# LED-Cube_v2.net
KiCad netlist of a schematic drawn in EAGLE
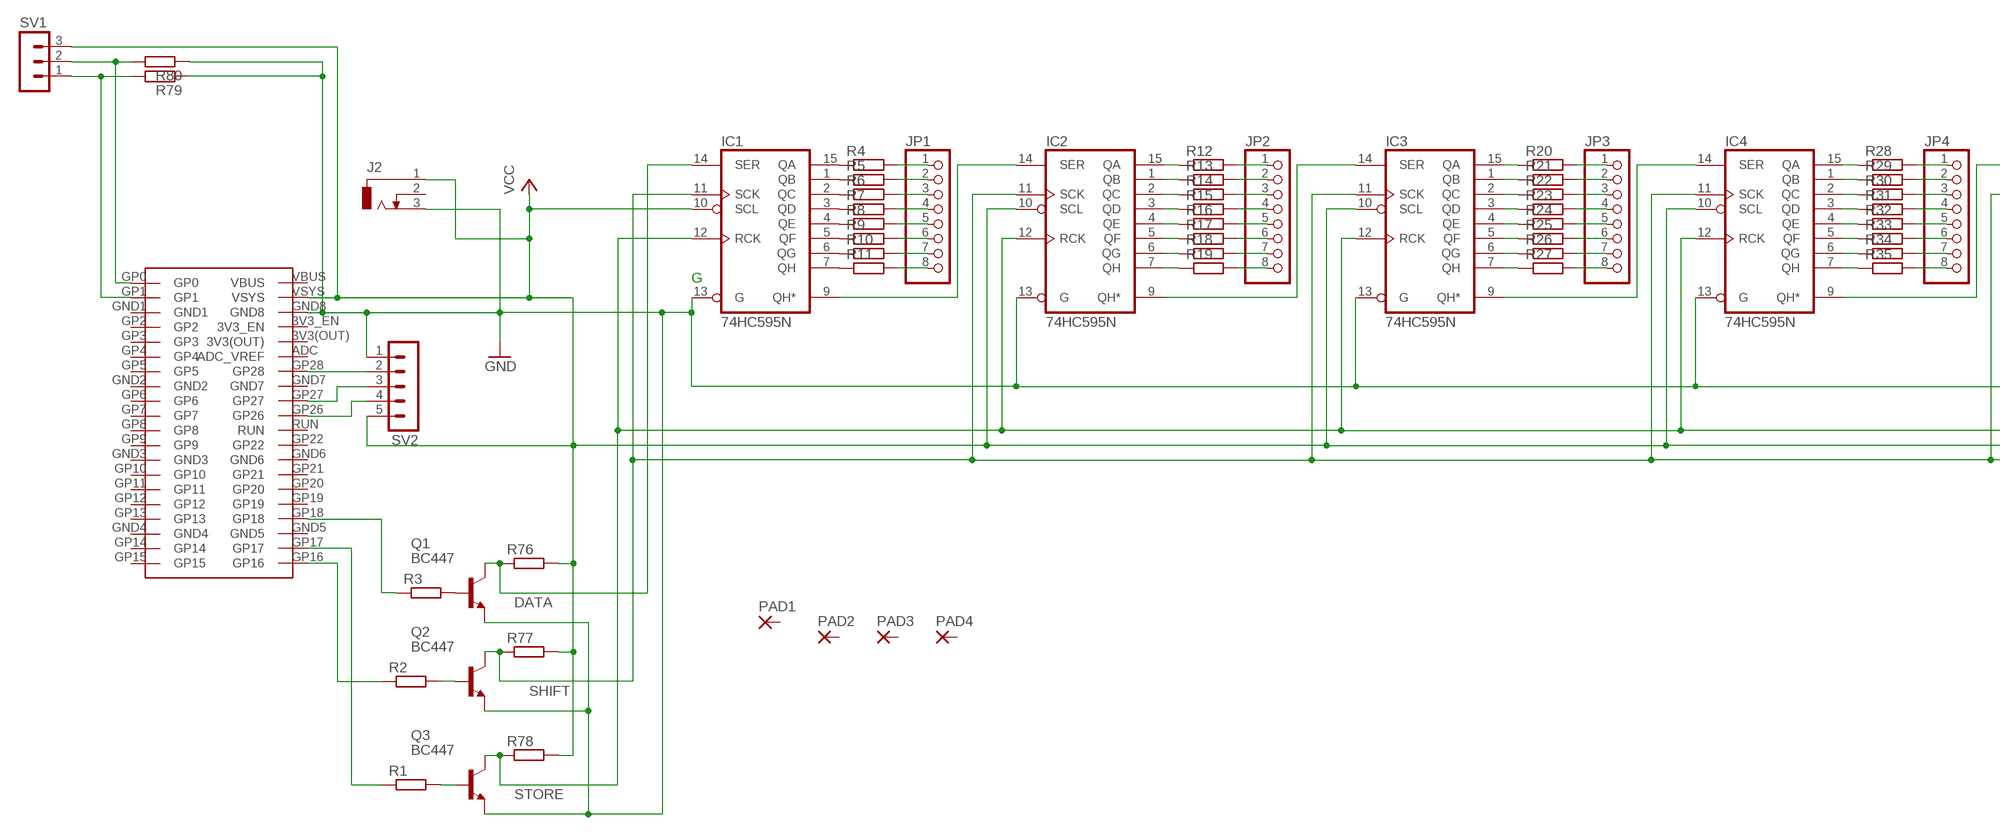
[diagram p0: schematic, sheet 1, part 1 of 2]
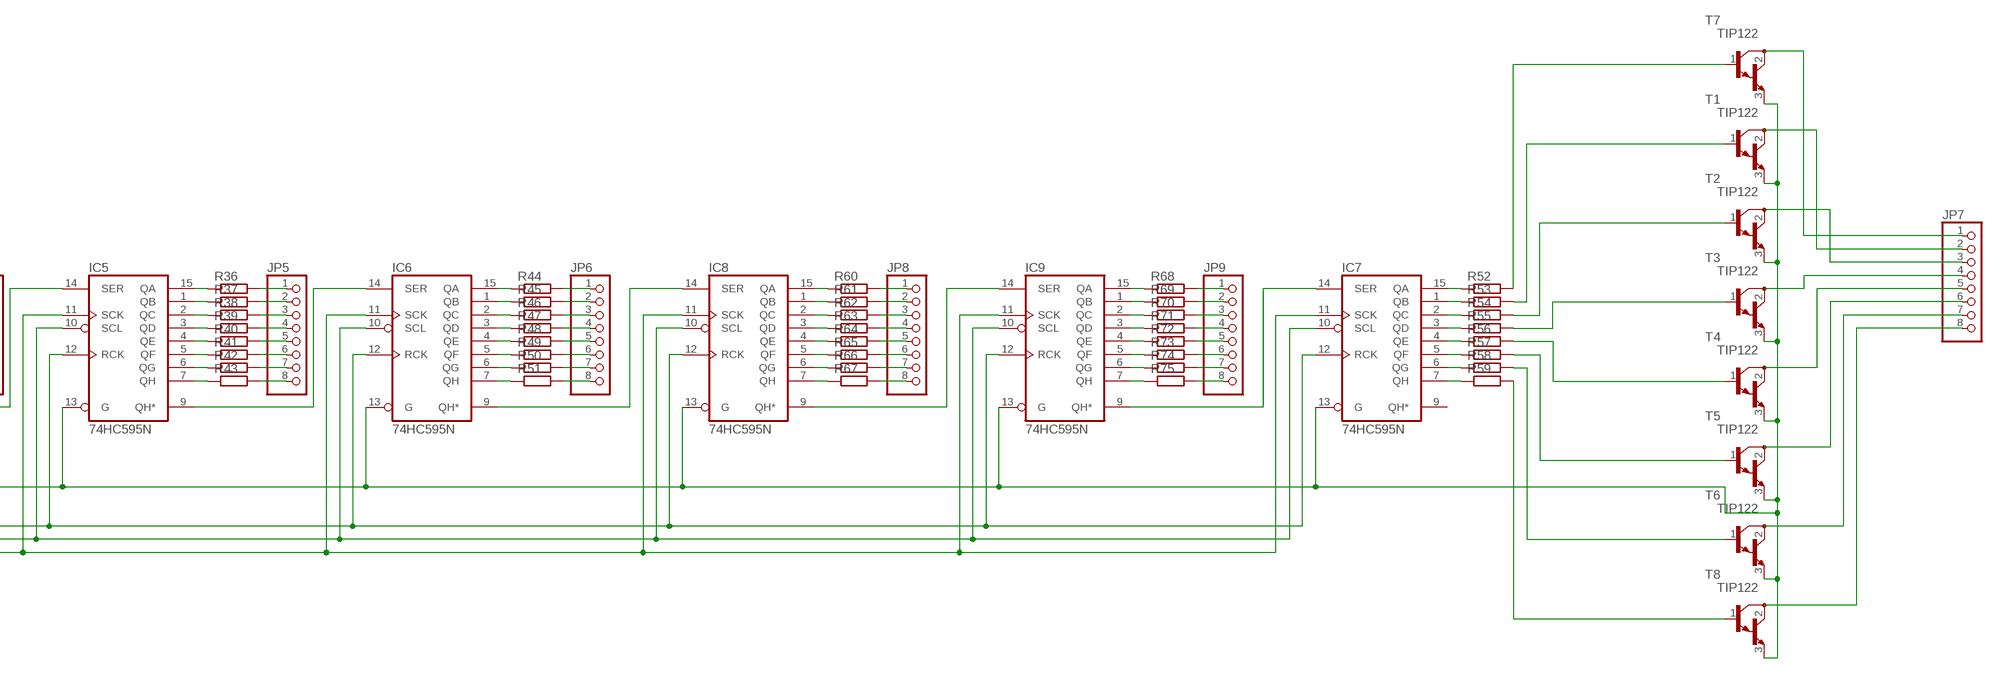
[diagram p1: schematic, sheet 1, part 2 of 2]

(export (version "E")
  (design (tool "Eeschema 10.0.6"))
  (components
    (comp (ref "IC1")
      (value "74HC595N")
      (footprint "eagle-import:DIL16")
      (libsource (lib "eagle-import") (part "74595NHC"))
    )
    (comp (ref "IC2")
      (value "74HC595N")
      (footprint "eagle-import:DIL16")
      (libsource (lib "eagle-import") (part "74595NHC"))
    )
    (comp (ref "IC3")
      (value "74HC595N")
      (footprint "eagle-import:DIL16")
      (libsource (lib "eagle-import") (part "74595NHC"))
    )
    (comp (ref "IC4")
      (value "74HC595N")
      (footprint "eagle-import:DIL16")
      (libsource (lib "eagle-import") (part "74595NHC"))
    )
    (comp (ref "IC5")
      (value "74HC595N")
      (footprint "eagle-import:DIL16")
      (libsource (lib "eagle-import") (part "74595NHC"))
    )
    (comp (ref "IC6")
      (value "74HC595N")
      (footprint "eagle-import:DIL16")
      (libsource (lib "eagle-import") (part "74595NHC"))
    )
    (comp (ref "IC7")
      (value "74HC595N")
      (footprint "eagle-import:DIL16")
      (libsource (lib "eagle-import") (part "74595NHC"))
    )
    (comp (ref "IC8")
      (value "74HC595N")
      (footprint "eagle-import:DIL16")
      (libsource (lib "eagle-import") (part "74595NHC"))
    )
    (comp (ref "IC9")
      (value "74HC595N")
      (footprint "eagle-import:DIL16")
      (libsource (lib "eagle-import") (part "74595NHC"))
    )
    (comp (ref "J2")
      (value "DCJ0303")
      (footprint "eagle-import:DCJ0303")
      (libsource (lib "eagle-import") (part "DCJ0303"))
    )
    (comp (ref "JP1")
      (value "PINHD-1X8")
      (footprint "eagle-import:1X08")
      (libsource (lib "eagle-import") (part "PINHD-1X8"))
    )
    (comp (ref "JP2")
      (value "PINHD-1X8")
      (footprint "eagle-import:1X08")
      (libsource (lib "eagle-import") (part "PINHD-1X8"))
    )
    (comp (ref "JP3")
      (value "PINHD-1X8")
      (footprint "eagle-import:1X08")
      (libsource (lib "eagle-import") (part "PINHD-1X8"))
    )
    (comp (ref "JP4")
      (value "PINHD-1X8")
      (footprint "eagle-import:1X08")
      (libsource (lib "eagle-import") (part "PINHD-1X8"))
    )
    (comp (ref "JP5")
      (value "PINHD-1X8")
      (footprint "eagle-import:1X08")
      (libsource (lib "eagle-import") (part "PINHD-1X8"))
    )
    (comp (ref "JP6")
      (value "PINHD-1X8")
      (footprint "eagle-import:1X08")
      (libsource (lib "eagle-import") (part "PINHD-1X8"))
    )
    (comp (ref "JP7")
      (value "PINHD-1X8")
      (footprint "eagle-import:1X08")
      (libsource (lib "eagle-import") (part "PINHD-1X8"))
    )
    (comp (ref "JP8")
      (value "PINHD-1X8")
      (footprint "eagle-import:1X08")
      (libsource (lib "eagle-import") (part "PINHD-1X8"))
    )
    (comp (ref "JP9")
      (value "PINHD-1X8")
      (footprint "eagle-import:1X08")
      (libsource (lib "eagle-import") (part "PINHD-1X8"))
    )
    (comp (ref "PAD1")
      (value "3,81/1,4")
      (footprint "eagle-import:3,81_1,4")
      (libsource (lib "eagle-import") (part "3,81/1,4"))
    )
    (comp (ref "PAD2")
      (value "3,81/1,4")
      (footprint "eagle-import:3,81_1,4")
      (libsource (lib "eagle-import") (part "3,81/1,4"))
    )
    (comp (ref "PAD3")
      (value "3,81/1,4")
      (footprint "eagle-import:3,81_1,4")
      (libsource (lib "eagle-import") (part "3,81/1,4"))
    )
    (comp (ref "PAD4")
      (value "3,81/1,4")
      (footprint "eagle-import:3,81_1,4")
      (libsource (lib "eagle-import") (part "3,81/1,4"))
    )
    (comp (ref "Q1")
      (value "BC447")
      (footprint "eagle-import:TO92-EBC")
      (libsource (lib "eagle-import") (part "BC447"))
    )
    (comp (ref "Q2")
      (value "BC447")
      (footprint "eagle-import:TO92-EBC")
      (libsource (lib "eagle-import") (part "BC447"))
    )
    (comp (ref "Q3")
      (value "BC447")
      (footprint "eagle-import:TO92-EBC")
      (libsource (lib "eagle-import") (part "BC447"))
    )
    (comp (ref "R1")
      (value "R-EU_0207/10")
      (footprint "eagle-import:0207_10")
      (libsource (lib "eagle-import") (part "R-EU_0207/10"))
    )
    (comp (ref "R2")
      (value "R-EU_0207/10")
      (footprint "eagle-import:0207_10")
      (libsource (lib "eagle-import") (part "R-EU_0207/10"))
    )
    (comp (ref "R3")
      (value "R-EU_0207/10")
      (footprint "eagle-import:0207_10")
      (libsource (lib "eagle-import") (part "R-EU_0207/10"))
    )
    (comp (ref "R4")
      (value "R-EU_0207/10")
      (footprint "eagle-import:0207_10")
      (libsource (lib "eagle-import") (part "R-EU_0207/10"))
    )
    (comp (ref "R5")
      (value "R-EU_0207/10")
      (footprint "eagle-import:0207_10")
      (libsource (lib "eagle-import") (part "R-EU_0207/10"))
    )
    (comp (ref "R6")
      (value "R-EU_0207/10")
      (footprint "eagle-import:0207_10")
      (libsource (lib "eagle-import") (part "R-EU_0207/10"))
    )
    (comp (ref "R7")
      (value "R-EU_0207/10")
      (footprint "eagle-import:0207_10")
      (libsource (lib "eagle-import") (part "R-EU_0207/10"))
    )
    (comp (ref "R8")
      (value "R-EU_0207/10")
      (footprint "eagle-import:0207_10")
      (libsource (lib "eagle-import") (part "R-EU_0207/10"))
    )
    (comp (ref "R9")
      (value "R-EU_0207/10")
      (footprint "eagle-import:0207_10")
      (libsource (lib "eagle-import") (part "R-EU_0207/10"))
    )
    (comp (ref "R10")
      (value "R-EU_0207/10")
      (footprint "eagle-import:0207_10")
      (libsource (lib "eagle-import") (part "R-EU_0207/10"))
    )
    (comp (ref "R11")
      (value "R-EU_0207/10")
      (footprint "eagle-import:0207_10")
      (libsource (lib "eagle-import") (part "R-EU_0207/10"))
    )
    (comp (ref "R12")
      (value "R-EU_0207/10")
      (footprint "eagle-import:0207_10")
      (libsource (lib "eagle-import") (part "R-EU_0207/10"))
    )
    (comp (ref "R13")
      (value "R-EU_0207/10")
      (footprint "eagle-import:0207_10")
      (libsource (lib "eagle-import") (part "R-EU_0207/10"))
    )
    (comp (ref "R14")
      (value "R-EU_0207/10")
      (footprint "eagle-import:0207_10")
      (libsource (lib "eagle-import") (part "R-EU_0207/10"))
    )
    (comp (ref "R15")
      (value "R-EU_0207/10")
      (footprint "eagle-import:0207_10")
      (libsource (lib "eagle-import") (part "R-EU_0207/10"))
    )
    (comp (ref "R16")
      (value "R-EU_0207/10")
      (footprint "eagle-import:0207_10")
      (libsource (lib "eagle-import") (part "R-EU_0207/10"))
    )
    (comp (ref "R17")
      (value "R-EU_0207/10")
      (footprint "eagle-import:0207_10")
      (libsource (lib "eagle-import") (part "R-EU_0207/10"))
    )
    (comp (ref "R18")
      (value "R-EU_0207/10")
      (footprint "eagle-import:0207_10")
      (libsource (lib "eagle-import") (part "R-EU_0207/10"))
    )
    (comp (ref "R19")
      (value "R-EU_0207/10")
      (footprint "eagle-import:0207_10")
      (libsource (lib "eagle-import") (part "R-EU_0207/10"))
    )
    (comp (ref "R20")
      (value "R-EU_0207/10")
      (footprint "eagle-import:0207_10")
      (libsource (lib "eagle-import") (part "R-EU_0207/10"))
    )
    (comp (ref "R21")
      (value "R-EU_0207/10")
      (footprint "eagle-import:0207_10")
      (libsource (lib "eagle-import") (part "R-EU_0207/10"))
    )
    (comp (ref "R22")
      (value "R-EU_0207/10")
      (footprint "eagle-import:0207_10")
      (libsource (lib "eagle-import") (part "R-EU_0207/10"))
    )
    (comp (ref "R23")
      (value "R-EU_0207/10")
      (footprint "eagle-import:0207_10")
      (libsource (lib "eagle-import") (part "R-EU_0207/10"))
    )
    (comp (ref "R24")
      (value "R-EU_0207/10")
      (footprint "eagle-import:0207_10")
      (libsource (lib "eagle-import") (part "R-EU_0207/10"))
    )
    (comp (ref "R25")
      (value "R-EU_0207/10")
      (footprint "eagle-import:0207_10")
      (libsource (lib "eagle-import") (part "R-EU_0207/10"))
    )
    (comp (ref "R26")
      (value "R-EU_0207/10")
      (footprint "eagle-import:0207_10")
      (libsource (lib "eagle-import") (part "R-EU_0207/10"))
    )
    (comp (ref "R27")
      (value "R-EU_0207/10")
      (footprint "eagle-import:0207_10")
      (libsource (lib "eagle-import") (part "R-EU_0207/10"))
    )
    (comp (ref "R28")
      (value "R-EU_0207/10")
      (footprint "eagle-import:0207_10")
      (libsource (lib "eagle-import") (part "R-EU_0207/10"))
    )
    (comp (ref "R29")
      (value "R-EU_0207/10")
      (footprint "eagle-import:0207_10")
      (libsource (lib "eagle-import") (part "R-EU_0207/10"))
    )
    (comp (ref "R30")
      (value "R-EU_0207/10")
      (footprint "eagle-import:0207_10")
      (libsource (lib "eagle-import") (part "R-EU_0207/10"))
    )
    (comp (ref "R31")
      (value "R-EU_0207/10")
      (footprint "eagle-import:0207_10")
      (libsource (lib "eagle-import") (part "R-EU_0207/10"))
    )
    (comp (ref "R32")
      (value "R-EU_0207/10")
      (footprint "eagle-import:0207_10")
      (libsource (lib "eagle-import") (part "R-EU_0207/10"))
    )
    (comp (ref "R33")
      (value "R-EU_0207/10")
      (footprint "eagle-import:0207_10")
      (libsource (lib "eagle-import") (part "R-EU_0207/10"))
    )
    (comp (ref "R34")
      (value "R-EU_0207/10")
      (footprint "eagle-import:0207_10")
      (libsource (lib "eagle-import") (part "R-EU_0207/10"))
    )
    (comp (ref "R35")
      (value "R-EU_0207/10")
      (footprint "eagle-import:0207_10")
      (libsource (lib "eagle-import") (part "R-EU_0207/10"))
    )
    (comp (ref "R36")
      (value "R-EU_0207/10")
      (footprint "eagle-import:0207_10")
      (libsource (lib "eagle-import") (part "R-EU_0207/10"))
    )
    (comp (ref "R37")
      (value "R-EU_0207/10")
      (footprint "eagle-import:0207_10")
      (libsource (lib "eagle-import") (part "R-EU_0207/10"))
    )
    (comp (ref "R38")
      (value "R-EU_0207/10")
      (footprint "eagle-import:0207_10")
      (libsource (lib "eagle-import") (part "R-EU_0207/10"))
    )
    (comp (ref "R39")
      (value "R-EU_0207/10")
      (footprint "eagle-import:0207_10")
      (libsource (lib "eagle-import") (part "R-EU_0207/10"))
    )
    (comp (ref "R40")
      (value "R-EU_0207/10")
      (footprint "eagle-import:0207_10")
      (libsource (lib "eagle-import") (part "R-EU_0207/10"))
    )
    (comp (ref "R41")
      (value "R-EU_0207/10")
      (footprint "eagle-import:0207_10")
      (libsource (lib "eagle-import") (part "R-EU_0207/10"))
    )
    (comp (ref "R42")
      (value "R-EU_0207/10")
      (footprint "eagle-import:0207_10")
      (libsource (lib "eagle-import") (part "R-EU_0207/10"))
    )
    (comp (ref "R43")
      (value "R-EU_0207/10")
      (footprint "eagle-import:0207_10")
      (libsource (lib "eagle-import") (part "R-EU_0207/10"))
    )
    (comp (ref "R44")
      (value "R-EU_0207/10")
      (footprint "eagle-import:0207_10")
      (libsource (lib "eagle-import") (part "R-EU_0207/10"))
    )
    (comp (ref "R45")
      (value "R-EU_0207/10")
      (footprint "eagle-import:0207_10")
      (libsource (lib "eagle-import") (part "R-EU_0207/10"))
    )
    (comp (ref "R46")
      (value "R-EU_0207/10")
      (footprint "eagle-import:0207_10")
      (libsource (lib "eagle-import") (part "R-EU_0207/10"))
    )
    (comp (ref "R47")
      (value "R-EU_0207/10")
      (footprint "eagle-import:0207_10")
      (libsource (lib "eagle-import") (part "R-EU_0207/10"))
    )
    (comp (ref "R48")
      (value "R-EU_0207/10")
      (footprint "eagle-import:0207_10")
      (libsource (lib "eagle-import") (part "R-EU_0207/10"))
    )
    (comp (ref "R49")
      (value "R-EU_0207/10")
      (footprint "eagle-import:0207_10")
      (libsource (lib "eagle-import") (part "R-EU_0207/10"))
    )
    (comp (ref "R50")
      (value "R-EU_0207/10")
      (footprint "eagle-import:0207_10")
      (libsource (lib "eagle-import") (part "R-EU_0207/10"))
    )
    (comp (ref "R51")
      (value "R-EU_0207/10")
      (footprint "eagle-import:0207_10")
      (libsource (lib "eagle-import") (part "R-EU_0207/10"))
    )
    (comp (ref "R52")
      (value "R-EU_0207/10")
      (footprint "eagle-import:0207_10")
      (libsource (lib "eagle-import") (part "R-EU_0207/10"))
    )
    (comp (ref "R53")
      (value "R-EU_0207/10")
      (footprint "eagle-import:0207_10")
      (libsource (lib "eagle-import") (part "R-EU_0207/10"))
    )
    (comp (ref "R54")
      (value "R-EU_0207/10")
      (footprint "eagle-import:0207_10")
      (libsource (lib "eagle-import") (part "R-EU_0207/10"))
    )
    (comp (ref "R55")
      (value "R-EU_0207/10")
      (footprint "eagle-import:0207_10")
      (libsource (lib "eagle-import") (part "R-EU_0207/10"))
    )
    (comp (ref "R56")
      (value "R-EU_0207/10")
      (footprint "eagle-import:0207_10")
      (libsource (lib "eagle-import") (part "R-EU_0207/10"))
    )
    (comp (ref "R57")
      (value "R-EU_0207/10")
      (footprint "eagle-import:0207_10")
      (libsource (lib "eagle-import") (part "R-EU_0207/10"))
    )
    (comp (ref "R58")
      (value "R-EU_0207/10")
      (footprint "eagle-import:0207_10")
      (libsource (lib "eagle-import") (part "R-EU_0207/10"))
    )
    (comp (ref "R59")
      (value "R-EU_0207/10")
      (footprint "eagle-import:0207_10")
      (libsource (lib "eagle-import") (part "R-EU_0207/10"))
    )
    (comp (ref "R60")
      (value "R-EU_0207/10")
      (footprint "eagle-import:0207_10")
      (libsource (lib "eagle-import") (part "R-EU_0207/10"))
    )
    (comp (ref "R61")
      (value "R-EU_0207/10")
      (footprint "eagle-import:0207_10")
      (libsource (lib "eagle-import") (part "R-EU_0207/10"))
    )
    (comp (ref "R62")
      (value "R-EU_0207/10")
      (footprint "eagle-import:0207_10")
      (libsource (lib "eagle-import") (part "R-EU_0207/10"))
    )
    (comp (ref "R63")
      (value "R-EU_0207/10")
      (footprint "eagle-import:0207_10")
      (libsource (lib "eagle-import") (part "R-EU_0207/10"))
    )
    (comp (ref "R64")
      (value "R-EU_0207/10")
      (footprint "eagle-import:0207_10")
      (libsource (lib "eagle-import") (part "R-EU_0207/10"))
    )
    (comp (ref "R65")
      (value "R-EU_0207/10")
      (footprint "eagle-import:0207_10")
      (libsource (lib "eagle-import") (part "R-EU_0207/10"))
    )
    (comp (ref "R66")
      (value "R-EU_0207/10")
      (footprint "eagle-import:0207_10")
      (libsource (lib "eagle-import") (part "R-EU_0207/10"))
    )
    (comp (ref "R67")
      (value "R-EU_0207/10")
      (footprint "eagle-import:0207_10")
      (libsource (lib "eagle-import") (part "R-EU_0207/10"))
    )
    (comp (ref "R68")
      (value "R-EU_0207/10")
      (footprint "eagle-import:0207_10")
      (libsource (lib "eagle-import") (part "R-EU_0207/10"))
    )
    (comp (ref "R69")
      (value "R-EU_0207/10")
      (footprint "eagle-import:0207_10")
      (libsource (lib "eagle-import") (part "R-EU_0207/10"))
    )
    (comp (ref "R70")
      (value "R-EU_0207/10")
      (footprint "eagle-import:0207_10")
      (libsource (lib "eagle-import") (part "R-EU_0207/10"))
    )
    (comp (ref "R71")
      (value "R-EU_0207/10")
      (footprint "eagle-import:0207_10")
      (libsource (lib "eagle-import") (part "R-EU_0207/10"))
    )
    (comp (ref "R72")
      (value "R-EU_0207/10")
      (footprint "eagle-import:0207_10")
      (libsource (lib "eagle-import") (part "R-EU_0207/10"))
    )
    (comp (ref "R73")
      (value "R-EU_0207/10")
      (footprint "eagle-import:0207_10")
      (libsource (lib "eagle-import") (part "R-EU_0207/10"))
    )
    (comp (ref "R74")
      (value "R-EU_0207/10")
      (footprint "eagle-import:0207_10")
      (libsource (lib "eagle-import") (part "R-EU_0207/10"))
    )
    (comp (ref "R75")
      (value "R-EU_0207/10")
      (footprint "eagle-import:0207_10")
      (libsource (lib "eagle-import") (part "R-EU_0207/10"))
    )
    (comp (ref "R76")
      (value "R-EU_0207/10")
      (footprint "eagle-import:0207_10")
      (libsource (lib "eagle-import") (part "R-EU_0207/10"))
    )
    (comp (ref "R77")
      (value "R-EU_0207/10")
      (footprint "eagle-import:0207_10")
      (libsource (lib "eagle-import") (part "R-EU_0207/10"))
    )
    (comp (ref "R78")
      (value "R-EU_0207/10")
      (footprint "eagle-import:0207_10")
      (libsource (lib "eagle-import") (part "R-EU_0207/10"))
    )
    (comp (ref "R79")
      (value "R-EU_0207/10")
      (footprint "eagle-import:0207_10")
      (libsource (lib "eagle-import") (part "R-EU_0207/10"))
    )
    (comp (ref "R80")
      (value "R-EU_0207/10")
      (footprint "eagle-import:0207_10")
      (libsource (lib "eagle-import") (part "R-EU_0207/10"))
    )
    (comp (ref "SV1")
      (value "MA03-1")
      (footprint "eagle-import:MA03-1")
      (libsource (lib "eagle-import") (part "MA03-1"))
    )
    (comp (ref "SV2")
      (value "MA05-1")
      (footprint "eagle-import:MA05-1")
      (libsource (lib "eagle-import") (part "MA05-1"))
    )
    (comp (ref "T1")
      (value "TIP122")
      (footprint "eagle-import:TO220")
      (libsource (lib "eagle-import") (part "TIP122"))
    )
    (comp (ref "T2")
      (value "TIP122")
      (footprint "eagle-import:TO220")
      (libsource (lib "eagle-import") (part "TIP122"))
    )
    (comp (ref "T3")
      (value "TIP122")
      (footprint "eagle-import:TO220")
      (libsource (lib "eagle-import") (part "TIP122"))
    )
    (comp (ref "T4")
      (value "TIP122")
      (footprint "eagle-import:TO220")
      (libsource (lib "eagle-import") (part "TIP122"))
    )
    (comp (ref "T5")
      (value "TIP122")
      (footprint "eagle-import:TO220")
      (libsource (lib "eagle-import") (part "TIP122"))
    )
    (comp (ref "T6")
      (value "TIP122")
      (footprint "eagle-import:TO220")
      (libsource (lib "eagle-import") (part "TIP122"))
    )
    (comp (ref "T7")
      (value "TIP122")
      (footprint "eagle-import:TO220")
      (libsource (lib "eagle-import") (part "TIP122"))
    )
    (comp (ref "T8")
      (value "TIP122")
      (footprint "eagle-import:TO220")
      (libsource (lib "eagle-import") (part "TIP122"))
    )
    (comp (ref "U$2")
      (value "PI_PICO")
      (footprint "eagle-import:PI_PICO")
      (libsource (lib "eagle-import") (part "PI_PICO"))
    )
  )
  (nets
    (net (code "1") (name "/DATA") (class "Default")
      (node (ref "IC1") (pin "14") (pinfunction "SER_14") (pintype "input"))
      (node (ref "Q1") (pin "C") (pinfunction "C_C") (pintype "passive"))
      (node (ref "R76") (pin "1") (pinfunction "1_1") (pintype "passive"))
    )
    (net (code "2") (name "/SHIFT") (class "Default")
      (node (ref "IC1") (pin "11") (pinfunction "SCK_11") (pintype "input"))
      (node (ref "IC2") (pin "11") (pinfunction "SCK_11") (pintype "input"))
      (node (ref "IC3") (pin "11") (pinfunction "SCK_11") (pintype "input"))
      (node (ref "IC4") (pin "11") (pinfunction "SCK_11") (pintype "input"))
      (node (ref "IC5") (pin "11") (pinfunction "SCK_11") (pintype "input"))
      (node (ref "IC6") (pin "11") (pinfunction "SCK_11") (pintype "input"))
      (node (ref "IC7") (pin "11") (pinfunction "SCK_11") (pintype "input"))
      (node (ref "IC8") (pin "11") (pinfunction "SCK_11") (pintype "input"))
      (node (ref "IC9") (pin "11") (pinfunction "SCK_11") (pintype "input"))
      (node (ref "Q2") (pin "C") (pinfunction "C_C") (pintype "passive"))
      (node (ref "R77") (pin "1") (pinfunction "1_1") (pintype "passive"))
    )
    (net (code "3") (name "/STORE") (class "Default")
      (node (ref "IC1") (pin "12") (pinfunction "RCK_12") (pintype "input"))
      (node (ref "IC2") (pin "12") (pinfunction "RCK_12") (pintype "input"))
      (node (ref "IC3") (pin "12") (pinfunction "RCK_12") (pintype "input"))
      (node (ref "IC4") (pin "12") (pinfunction "RCK_12") (pintype "input"))
      (node (ref "IC5") (pin "12") (pinfunction "RCK_12") (pintype "input"))
      (node (ref "IC6") (pin "12") (pinfunction "RCK_12") (pintype "input"))
      (node (ref "IC7") (pin "12") (pinfunction "RCK_12") (pintype "input"))
      (node (ref "IC8") (pin "12") (pinfunction "RCK_12") (pintype "input"))
      (node (ref "IC9") (pin "12") (pinfunction "RCK_12") (pintype "input"))
      (node (ref "Q3") (pin "C") (pinfunction "C_C") (pintype "passive"))
      (node (ref "R78") (pin "1") (pinfunction "1_1") (pintype "passive"))
    )
    (net (code "4") (name "GND") (class "Default")
      (node (ref "IC1") (pin "13") (pinfunction "G_13") (pintype "input"))
      (node (ref "IC2") (pin "13") (pinfunction "G_13") (pintype "input"))
      (node (ref "IC3") (pin "13") (pinfunction "G_13") (pintype "input"))
      (node (ref "IC4") (pin "13") (pinfunction "G_13") (pintype "input"))
      (node (ref "IC5") (pin "13") (pinfunction "G_13") (pintype "input"))
      (node (ref "IC6") (pin "13") (pinfunction "G_13") (pintype "input"))
      (node (ref "IC7") (pin "13") (pinfunction "G_13") (pintype "input"))
      (node (ref "IC8") (pin "13") (pinfunction "G_13") (pintype "input"))
      (node (ref "IC9") (pin "13") (pinfunction "G_13") (pintype "input"))
      (node (ref "J2") (pin "3") (pinfunction "3_3") (pintype "passive"))
      (node (ref "Q1") (pin "E") (pinfunction "E_E") (pintype "passive"))
      (node (ref "Q2") (pin "E") (pinfunction "E_E") (pintype "passive"))
      (node (ref "Q3") (pin "E") (pinfunction "E_E") (pintype "passive"))
      (node (ref "R79") (pin "1") (pinfunction "1_1") (pintype "passive"))
      (node (ref "R80") (pin "1") (pinfunction "1_1") (pintype "passive"))
      (node (ref "SV2") (pin "1") (pinfunction "1_1") (pintype "passive"))
      (node (ref "T1") (pin "3") (pinfunction "E_3") (pintype "passive"))
      (node (ref "T2") (pin "3") (pinfunction "E_3") (pintype "passive"))
      (node (ref "T3") (pin "3") (pinfunction "E_3") (pintype "passive"))
      (node (ref "T4") (pin "3") (pinfunction "E_3") (pintype "passive"))
      (node (ref "T5") (pin "3") (pinfunction "E_3") (pintype "passive"))
      (node (ref "T6") (pin "3") (pinfunction "E_3") (pintype "passive"))
      (node (ref "T7") (pin "3") (pinfunction "E_3") (pintype "passive"))
      (node (ref "T8") (pin "3") (pinfunction "E_3") (pintype "passive"))
      (node (ref "U$2") (pin "GND8") (pinfunction "GND8_GND8") (pintype "bidirectional"))
    )
    (net (code "5") (name "Net-(IC1A-QA)") (class "Default")
      (node (ref "IC1") (pin "15") (pinfunction "QA_15") (pintype "tri_state"))
      (node (ref "R4") (pin "1") (pinfunction "1_1") (pintype "passive"))
    )
    (net (code "6") (name "Net-(IC1A-QB)") (class "Default")
      (node (ref "IC1") (pin "1") (pinfunction "QB_1") (pintype "tri_state"))
      (node (ref "R5") (pin "1") (pinfunction "1_1") (pintype "passive"))
    )
    (net (code "7") (name "Net-(IC1A-QC)") (class "Default")
      (node (ref "IC1") (pin "2") (pinfunction "QC_2") (pintype "tri_state"))
      (node (ref "R6") (pin "1") (pinfunction "1_1") (pintype "passive"))
    )
    (net (code "8") (name "Net-(IC1A-QD)") (class "Default")
      (node (ref "IC1") (pin "3") (pinfunction "QD_3") (pintype "tri_state"))
      (node (ref "R7") (pin "1") (pinfunction "1_1") (pintype "passive"))
    )
    (net (code "9") (name "Net-(IC1A-QE)") (class "Default")
      (node (ref "IC1") (pin "4") (pinfunction "QE_4") (pintype "tri_state"))
      (node (ref "R8") (pin "1") (pinfunction "1_1") (pintype "passive"))
    )
    (net (code "10") (name "Net-(IC1A-QF)") (class "Default")
      (node (ref "IC1") (pin "5") (pinfunction "QF_5") (pintype "tri_state"))
      (node (ref "R9") (pin "1") (pinfunction "1_1") (pintype "passive"))
    )
    (net (code "11") (name "Net-(IC1A-QG)") (class "Default")
      (node (ref "IC1") (pin "6") (pinfunction "QG_6") (pintype "tri_state"))
      (node (ref "R10") (pin "1") (pinfunction "1_1") (pintype "passive"))
    )
    (net (code "12") (name "Net-(IC1A-QH)") (class "Default")
      (node (ref "IC1") (pin "7") (pinfunction "QH_7") (pintype "tri_state"))
      (node (ref "R11") (pin "1") (pinfunction "1_1") (pintype "passive"))
    )
    (net (code "13") (name "Net-(IC1A-QH*)") (class "Default")
      (node (ref "IC1") (pin "9") (pinfunction "QH*_9") (pintype "tri_state"))
      (node (ref "IC2") (pin "14") (pinfunction "SER_14") (pintype "input"))
    )
    (net (code "14") (name "Net-(IC2A-QA)") (class "Default")
      (node (ref "IC2") (pin "15") (pinfunction "QA_15") (pintype "tri_state"))
      (node (ref "R12") (pin "1") (pinfunction "1_1") (pintype "passive"))
    )
    (net (code "15") (name "Net-(IC2A-QB)") (class "Default")
      (node (ref "IC2") (pin "1") (pinfunction "QB_1") (pintype "tri_state"))
      (node (ref "R13") (pin "1") (pinfunction "1_1") (pintype "passive"))
    )
    (net (code "16") (name "Net-(IC2A-QC)") (class "Default")
      (node (ref "IC2") (pin "2") (pinfunction "QC_2") (pintype "tri_state"))
      (node (ref "R14") (pin "1") (pinfunction "1_1") (pintype "passive"))
    )
    (net (code "17") (name "Net-(IC2A-QD)") (class "Default")
      (node (ref "IC2") (pin "3") (pinfunction "QD_3") (pintype "tri_state"))
      (node (ref "R15") (pin "1") (pinfunction "1_1") (pintype "passive"))
    )
    (net (code "18") (name "Net-(IC2A-QE)") (class "Default")
      (node (ref "IC2") (pin "4") (pinfunction "QE_4") (pintype "tri_state"))
      (node (ref "R16") (pin "1") (pinfunction "1_1") (pintype "passive"))
    )
    (net (code "19") (name "Net-(IC2A-QF)") (class "Default")
      (node (ref "IC2") (pin "5") (pinfunction "QF_5") (pintype "tri_state"))
      (node (ref "R17") (pin "1") (pinfunction "1_1") (pintype "passive"))
    )
    (net (code "20") (name "Net-(IC2A-QG)") (class "Default")
      (node (ref "IC2") (pin "6") (pinfunction "QG_6") (pintype "tri_state"))
      (node (ref "R18") (pin "1") (pinfunction "1_1") (pintype "passive"))
    )
    (net (code "21") (name "Net-(IC2A-QH)") (class "Default")
      (node (ref "IC2") (pin "7") (pinfunction "QH_7") (pintype "tri_state"))
      (node (ref "R19") (pin "1") (pinfunction "1_1") (pintype "passive"))
    )
    (net (code "22") (name "Net-(IC2A-QH*)") (class "Default")
      (node (ref "IC2") (pin "9") (pinfunction "QH*_9") (pintype "tri_state"))
      (node (ref "IC3") (pin "14") (pinfunction "SER_14") (pintype "input"))
    )
    (net (code "23") (name "Net-(IC3A-QA)") (class "Default")
      (node (ref "IC3") (pin "15") (pinfunction "QA_15") (pintype "tri_state"))
      (node (ref "R20") (pin "1") (pinfunction "1_1") (pintype "passive"))
    )
    (net (code "24") (name "Net-(IC3A-QB)") (class "Default")
      (node (ref "IC3") (pin "1") (pinfunction "QB_1") (pintype "tri_state"))
      (node (ref "R21") (pin "1") (pinfunction "1_1") (pintype "passive"))
    )
    (net (code "25") (name "Net-(IC3A-QC)") (class "Default")
      (node (ref "IC3") (pin "2") (pinfunction "QC_2") (pintype "tri_state"))
      (node (ref "R22") (pin "1") (pinfunction "1_1") (pintype "passive"))
    )
    (net (code "26") (name "Net-(IC3A-QD)") (class "Default")
      (node (ref "IC3") (pin "3") (pinfunction "QD_3") (pintype "tri_state"))
      (node (ref "R23") (pin "1") (pinfunction "1_1") (pintype "passive"))
    )
    (net (code "27") (name "Net-(IC3A-QE)") (class "Default")
      (node (ref "IC3") (pin "4") (pinfunction "QE_4") (pintype "tri_state"))
      (node (ref "R24") (pin "1") (pinfunction "1_1") (pintype "passive"))
    )
    (net (code "28") (name "Net-(IC3A-QF)") (class "Default")
      (node (ref "IC3") (pin "5") (pinfunction "QF_5") (pintype "tri_state"))
      (node (ref "R25") (pin "1") (pinfunction "1_1") (pintype "passive"))
    )
    (net (code "29") (name "Net-(IC3A-QG)") (class "Default")
      (node (ref "IC3") (pin "6") (pinfunction "QG_6") (pintype "tri_state"))
      (node (ref "R26") (pin "1") (pinfunction "1_1") (pintype "passive"))
    )
    (net (code "30") (name "Net-(IC3A-QH)") (class "Default")
      (node (ref "IC3") (pin "7") (pinfunction "QH_7") (pintype "tri_state"))
      (node (ref "R27") (pin "1") (pinfunction "1_1") (pintype "passive"))
    )
    (net (code "31") (name "Net-(IC3A-QH*)") (class "Default")
      (node (ref "IC3") (pin "9") (pinfunction "QH*_9") (pintype "tri_state"))
      (node (ref "IC4") (pin "14") (pinfunction "SER_14") (pintype "input"))
    )
    (net (code "32") (name "Net-(IC4A-QA)") (class "Default")
      (node (ref "IC4") (pin "15") (pinfunction "QA_15") (pintype "tri_state"))
      (node (ref "R28") (pin "1") (pinfunction "1_1") (pintype "passive"))
    )
    (net (code "33") (name "Net-(IC4A-QB)") (class "Default")
      (node (ref "IC4") (pin "1") (pinfunction "QB_1") (pintype "tri_state"))
      (node (ref "R29") (pin "1") (pinfunction "1_1") (pintype "passive"))
    )
    (net (code "34") (name "Net-(IC4A-QC)") (class "Default")
      (node (ref "IC4") (pin "2") (pinfunction "QC_2") (pintype "tri_state"))
      (node (ref "R30") (pin "1") (pinfunction "1_1") (pintype "passive"))
    )
    (net (code "35") (name "Net-(IC4A-QD)") (class "Default")
      (node (ref "IC4") (pin "3") (pinfunction "QD_3") (pintype "tri_state"))
      (node (ref "R31") (pin "1") (pinfunction "1_1") (pintype "passive"))
    )
    (net (code "36") (name "Net-(IC4A-QE)") (class "Default")
      (node (ref "IC4") (pin "4") (pinfunction "QE_4") (pintype "tri_state"))
      (node (ref "R32") (pin "1") (pinfunction "1_1") (pintype "passive"))
    )
    (net (code "37") (name "Net-(IC4A-QF)") (class "Default")
      (node (ref "IC4") (pin "5") (pinfunction "QF_5") (pintype "tri_state"))
      (node (ref "R33") (pin "1") (pinfunction "1_1") (pintype "passive"))
    )
    (net (code "38") (name "Net-(IC4A-QG)") (class "Default")
      (node (ref "IC4") (pin "6") (pinfunction "QG_6") (pintype "tri_state"))
      (node (ref "R34") (pin "1") (pinfunction "1_1") (pintype "passive"))
    )
    (net (code "39") (name "Net-(IC4A-QH)") (class "Default")
      (node (ref "IC4") (pin "7") (pinfunction "QH_7") (pintype "tri_state"))
      (node (ref "R35") (pin "1") (pinfunction "1_1") (pintype "passive"))
    )
    (net (code "40") (name "Net-(IC4A-QH*)") (class "Default")
      (node (ref "IC4") (pin "9") (pinfunction "QH*_9") (pintype "tri_state"))
      (node (ref "IC5") (pin "14") (pinfunction "SER_14") (pintype "input"))
    )
    (net (code "41") (name "Net-(IC5A-QA)") (class "Default")
      (node (ref "IC5") (pin "15") (pinfunction "QA_15") (pintype "tri_state"))
      (node (ref "R36") (pin "1") (pinfunction "1_1") (pintype "passive"))
    )
    (net (code "42") (name "Net-(IC5A-QB)") (class "Default")
      (node (ref "IC5") (pin "1") (pinfunction "QB_1") (pintype "tri_state"))
      (node (ref "R37") (pin "1") (pinfunction "1_1") (pintype "passive"))
    )
    (net (code "43") (name "Net-(IC5A-QC)") (class "Default")
      (node (ref "IC5") (pin "2") (pinfunction "QC_2") (pintype "tri_state"))
      (node (ref "R38") (pin "1") (pinfunction "1_1") (pintype "passive"))
    )
    (net (code "44") (name "Net-(IC5A-QD)") (class "Default")
      (node (ref "IC5") (pin "3") (pinfunction "QD_3") (pintype "tri_state"))
      (node (ref "R39") (pin "1") (pinfunction "1_1") (pintype "passive"))
    )
    (net (code "45") (name "Net-(IC5A-QE)") (class "Default")
      (node (ref "IC5") (pin "4") (pinfunction "QE_4") (pintype "tri_state"))
      (node (ref "R40") (pin "1") (pinfunction "1_1") (pintype "passive"))
    )
    (net (code "46") (name "Net-(IC5A-QF)") (class "Default")
      (node (ref "IC5") (pin "5") (pinfunction "QF_5") (pintype "tri_state"))
      (node (ref "R41") (pin "1") (pinfunction "1_1") (pintype "passive"))
    )
    (net (code "47") (name "Net-(IC5A-QG)") (class "Default")
      (node (ref "IC5") (pin "6") (pinfunction "QG_6") (pintype "tri_state"))
      (node (ref "R42") (pin "1") (pinfunction "1_1") (pintype "passive"))
    )
    (net (code "48") (name "Net-(IC5A-QH)") (class "Default")
      (node (ref "IC5") (pin "7") (pinfunction "QH_7") (pintype "tri_state"))
      (node (ref "R43") (pin "1") (pinfunction "1_1") (pintype "passive"))
    )
    (net (code "49") (name "Net-(IC5A-QH*)") (class "Default")
      (node (ref "IC5") (pin "9") (pinfunction "QH*_9") (pintype "tri_state"))
      (node (ref "IC6") (pin "14") (pinfunction "SER_14") (pintype "input"))
    )
    (net (code "50") (name "Net-(IC6A-QA)") (class "Default")
      (node (ref "IC6") (pin "15") (pinfunction "QA_15") (pintype "tri_state"))
      (node (ref "R44") (pin "1") (pinfunction "1_1") (pintype "passive"))
    )
    (net (code "51") (name "Net-(IC6A-QB)") (class "Default")
      (node (ref "IC6") (pin "1") (pinfunction "QB_1") (pintype "tri_state"))
      (node (ref "R45") (pin "1") (pinfunction "1_1") (pintype "passive"))
    )
    (net (code "52") (name "Net-(IC6A-QC)") (class "Default")
      (node (ref "IC6") (pin "2") (pinfunction "QC_2") (pintype "tri_state"))
      (node (ref "R46") (pin "1") (pinfunction "1_1") (pintype "passive"))
    )
    (net (code "53") (name "Net-(IC6A-QD)") (class "Default")
      (node (ref "IC6") (pin "3") (pinfunction "QD_3") (pintype "tri_state"))
      (node (ref "R47") (pin "1") (pinfunction "1_1") (pintype "passive"))
    )
    (net (code "54") (name "Net-(IC6A-QE)") (class "Default")
      (node (ref "IC6") (pin "4") (pinfunction "QE_4") (pintype "tri_state"))
      (node (ref "R48") (pin "1") (pinfunction "1_1") (pintype "passive"))
    )
    (net (code "55") (name "Net-(IC6A-QF)") (class "Default")
      (node (ref "IC6") (pin "5") (pinfunction "QF_5") (pintype "tri_state"))
      (node (ref "R49") (pin "1") (pinfunction "1_1") (pintype "passive"))
    )
    (net (code "56") (name "Net-(IC6A-QG)") (class "Default")
      (node (ref "IC6") (pin "6") (pinfunction "QG_6") (pintype "tri_state"))
      (node (ref "R50") (pin "1") (pinfunction "1_1") (pintype "passive"))
    )
    (net (code "57") (name "Net-(IC6A-QH)") (class "Default")
      (node (ref "IC6") (pin "7") (pinfunction "QH_7") (pintype "tri_state"))
      (node (ref "R51") (pin "1") (pinfunction "1_1") (pintype "passive"))
    )
    (net (code "58") (name "Net-(IC6A-QH*)") (class "Default")
      (node (ref "IC6") (pin "9") (pinfunction "QH*_9") (pintype "tri_state"))
      (node (ref "IC8") (pin "14") (pinfunction "SER_14") (pintype "input"))
    )
    (net (code "59") (name "Net-(IC7A-QA)") (class "Default")
      (node (ref "IC7") (pin "15") (pinfunction "QA_15") (pintype "tri_state"))
      (node (ref "R52") (pin "1") (pinfunction "1_1") (pintype "passive"))
    )
    (net (code "60") (name "Net-(IC7A-QB)") (class "Default")
      (node (ref "IC7") (pin "1") (pinfunction "QB_1") (pintype "tri_state"))
      (node (ref "R53") (pin "1") (pinfunction "1_1") (pintype "passive"))
    )
    (net (code "61") (name "Net-(IC7A-QC)") (class "Default")
      (node (ref "IC7") (pin "2") (pinfunction "QC_2") (pintype "tri_state"))
      (node (ref "R54") (pin "1") (pinfunction "1_1") (pintype "passive"))
    )
    (net (code "62") (name "Net-(IC7A-QD)") (class "Default")
      (node (ref "IC7") (pin "3") (pinfunction "QD_3") (pintype "tri_state"))
      (node (ref "R55") (pin "1") (pinfunction "1_1") (pintype "passive"))
    )
    (net (code "63") (name "Net-(IC7A-QE)") (class "Default")
      (node (ref "IC7") (pin "4") (pinfunction "QE_4") (pintype "tri_state"))
      (node (ref "R56") (pin "1") (pinfunction "1_1") (pintype "passive"))
    )
    (net (code "64") (name "Net-(IC7A-QF)") (class "Default")
      (node (ref "IC7") (pin "5") (pinfunction "QF_5") (pintype "tri_state"))
      (node (ref "R57") (pin "1") (pinfunction "1_1") (pintype "passive"))
    )
    (net (code "65") (name "Net-(IC7A-QG)") (class "Default")
      (node (ref "IC7") (pin "6") (pinfunction "QG_6") (pintype "tri_state"))
      (node (ref "R58") (pin "1") (pinfunction "1_1") (pintype "passive"))
    )
    (net (code "66") (name "Net-(IC7A-QH)") (class "Default")
      (node (ref "IC7") (pin "7") (pinfunction "QH_7") (pintype "tri_state"))
      (node (ref "R59") (pin "1") (pinfunction "1_1") (pintype "passive"))
    )
    (net (code "67") (name "Net-(IC7A-SER)") (class "Default")
      (node (ref "IC7") (pin "14") (pinfunction "SER_14") (pintype "input"))
      (node (ref "IC9") (pin "9") (pinfunction "QH*_9") (pintype "tri_state"))
    )
    (net (code "68") (name "Net-(IC8A-QA)") (class "Default")
      (node (ref "IC8") (pin "15") (pinfunction "QA_15") (pintype "tri_state"))
      (node (ref "R60") (pin "1") (pinfunction "1_1") (pintype "passive"))
    )
    (net (code "69") (name "Net-(IC8A-QB)") (class "Default")
      (node (ref "IC8") (pin "1") (pinfunction "QB_1") (pintype "tri_state"))
      (node (ref "R61") (pin "1") (pinfunction "1_1") (pintype "passive"))
    )
    (net (code "70") (name "Net-(IC8A-QC)") (class "Default")
      (node (ref "IC8") (pin "2") (pinfunction "QC_2") (pintype "tri_state"))
      (node (ref "R62") (pin "1") (pinfunction "1_1") (pintype "passive"))
    )
    (net (code "71") (name "Net-(IC8A-QD)") (class "Default")
      (node (ref "IC8") (pin "3") (pinfunction "QD_3") (pintype "tri_state"))
      (node (ref "R63") (pin "1") (pinfunction "1_1") (pintype "passive"))
    )
    (net (code "72") (name "Net-(IC8A-QE)") (class "Default")
      (node (ref "IC8") (pin "4") (pinfunction "QE_4") (pintype "tri_state"))
      (node (ref "R64") (pin "1") (pinfunction "1_1") (pintype "passive"))
    )
    (net (code "73") (name "Net-(IC8A-QF)") (class "Default")
      (node (ref "IC8") (pin "5") (pinfunction "QF_5") (pintype "tri_state"))
      (node (ref "R65") (pin "1") (pinfunction "1_1") (pintype "passive"))
    )
    (net (code "74") (name "Net-(IC8A-QG)") (class "Default")
      (node (ref "IC8") (pin "6") (pinfunction "QG_6") (pintype "tri_state"))
      (node (ref "R66") (pin "1") (pinfunction "1_1") (pintype "passive"))
    )
    (net (code "75") (name "Net-(IC8A-QH)") (class "Default")
      (node (ref "IC8") (pin "7") (pinfunction "QH_7") (pintype "tri_state"))
      (node (ref "R67") (pin "1") (pinfunction "1_1") (pintype "passive"))
    )
    (net (code "76") (name "Net-(IC8A-QH*)") (class "Default")
      (node (ref "IC8") (pin "9") (pinfunction "QH*_9") (pintype "tri_state"))
      (node (ref "IC9") (pin "14") (pinfunction "SER_14") (pintype "input"))
    )
    (net (code "77") (name "Net-(IC9A-QA)") (class "Default")
      (node (ref "IC9") (pin "15") (pinfunction "QA_15") (pintype "tri_state"))
      (node (ref "R68") (pin "1") (pinfunction "1_1") (pintype "passive"))
    )
    (net (code "78") (name "Net-(IC9A-QB)") (class "Default")
      (node (ref "IC9") (pin "1") (pinfunction "QB_1") (pintype "tri_state"))
      (node (ref "R69") (pin "1") (pinfunction "1_1") (pintype "passive"))
    )
    (net (code "79") (name "Net-(IC9A-QC)") (class "Default")
      (node (ref "IC9") (pin "2") (pinfunction "QC_2") (pintype "tri_state"))
      (node (ref "R70") (pin "1") (pinfunction "1_1") (pintype "passive"))
    )
    (net (code "80") (name "Net-(IC9A-QD)") (class "Default")
      (node (ref "IC9") (pin "3") (pinfunction "QD_3") (pintype "tri_state"))
      (node (ref "R71") (pin "1") (pinfunction "1_1") (pintype "passive"))
    )
    (net (code "81") (name "Net-(IC9A-QE)") (class "Default")
      (node (ref "IC9") (pin "4") (pinfunction "QE_4") (pintype "tri_state"))
      (node (ref "R72") (pin "1") (pinfunction "1_1") (pintype "passive"))
    )
    (net (code "82") (name "Net-(IC9A-QF)") (class "Default")
      (node (ref "IC9") (pin "5") (pinfunction "QF_5") (pintype "tri_state"))
      (node (ref "R73") (pin "1") (pinfunction "1_1") (pintype "passive"))
    )
    (net (code "83") (name "Net-(IC9A-QG)") (class "Default")
      (node (ref "IC9") (pin "6") (pinfunction "QG_6") (pintype "tri_state"))
      (node (ref "R74") (pin "1") (pinfunction "1_1") (pintype "passive"))
    )
    (net (code "84") (name "Net-(IC9A-QH)") (class "Default")
      (node (ref "IC9") (pin "7") (pinfunction "QH_7") (pintype "tri_state"))
      (node (ref "R75") (pin "1") (pinfunction "1_1") (pintype "passive"))
    )
    (net (code "85") (name "Net-(JP1-Pad1)") (class "Default")
      (node (ref "JP1") (pin "1") (pinfunction "1_1") (pintype "passive"))
      (node (ref "R4") (pin "2") (pinfunction "2_2") (pintype "passive"))
    )
    (net (code "86") (name "Net-(JP1-Pad2)") (class "Default")
      (node (ref "JP1") (pin "2") (pinfunction "2_2") (pintype "passive"))
      (node (ref "R5") (pin "2") (pinfunction "2_2") (pintype "passive"))
    )
    (net (code "87") (name "Net-(JP1-Pad3)") (class "Default")
      (node (ref "JP1") (pin "3") (pinfunction "3_3") (pintype "passive"))
      (node (ref "R6") (pin "2") (pinfunction "2_2") (pintype "passive"))
    )
    (net (code "88") (name "Net-(JP1-Pad4)") (class "Default")
      (node (ref "JP1") (pin "4") (pinfunction "4_4") (pintype "passive"))
      (node (ref "R7") (pin "2") (pinfunction "2_2") (pintype "passive"))
    )
    (net (code "89") (name "Net-(JP1-Pad5)") (class "Default")
      (node (ref "JP1") (pin "5") (pinfunction "5_5") (pintype "passive"))
      (node (ref "R8") (pin "2") (pinfunction "2_2") (pintype "passive"))
    )
    (net (code "90") (name "Net-(JP1-Pad6)") (class "Default")
      (node (ref "JP1") (pin "6") (pinfunction "6_6") (pintype "passive"))
      (node (ref "R9") (pin "2") (pinfunction "2_2") (pintype "passive"))
    )
    (net (code "91") (name "Net-(JP1-Pad7)") (class "Default")
      (node (ref "JP1") (pin "7") (pinfunction "7_7") (pintype "passive"))
      (node (ref "R10") (pin "2") (pinfunction "2_2") (pintype "passive"))
    )
    (net (code "92") (name "Net-(JP1-Pad8)") (class "Default")
      (node (ref "JP1") (pin "8") (pinfunction "8_8") (pintype "passive"))
      (node (ref "R11") (pin "2") (pinfunction "2_2") (pintype "passive"))
    )
    (net (code "93") (name "Net-(JP2-Pad1)") (class "Default")
      (node (ref "JP2") (pin "1") (pinfunction "1_1") (pintype "passive"))
      (node (ref "R12") (pin "2") (pinfunction "2_2") (pintype "passive"))
    )
    (net (code "94") (name "Net-(JP2-Pad2)") (class "Default")
      (node (ref "JP2") (pin "2") (pinfunction "2_2") (pintype "passive"))
      (node (ref "R13") (pin "2") (pinfunction "2_2") (pintype "passive"))
    )
    (net (code "95") (name "Net-(JP2-Pad3)") (class "Default")
      (node (ref "JP2") (pin "3") (pinfunction "3_3") (pintype "passive"))
      (node (ref "R14") (pin "2") (pinfunction "2_2") (pintype "passive"))
    )
    (net (code "96") (name "Net-(JP2-Pad4)") (class "Default")
      (node (ref "JP2") (pin "4") (pinfunction "4_4") (pintype "passive"))
      (node (ref "R15") (pin "2") (pinfunction "2_2") (pintype "passive"))
    )
    (net (code "97") (name "Net-(JP2-Pad5)") (class "Default")
      (node (ref "JP2") (pin "5") (pinfunction "5_5") (pintype "passive"))
      (node (ref "R16") (pin "2") (pinfunction "2_2") (pintype "passive"))
    )
    (net (code "98") (name "Net-(JP2-Pad6)") (class "Default")
      (node (ref "JP2") (pin "6") (pinfunction "6_6") (pintype "passive"))
      (node (ref "R17") (pin "2") (pinfunction "2_2") (pintype "passive"))
    )
    (net (code "99") (name "Net-(JP2-Pad7)") (class "Default")
      (node (ref "JP2") (pin "7") (pinfunction "7_7") (pintype "passive"))
      (node (ref "R18") (pin "2") (pinfunction "2_2") (pintype "passive"))
    )
    (net (code "100") (name "Net-(JP2-Pad8)") (class "Default")
      (node (ref "JP2") (pin "8") (pinfunction "8_8") (pintype "passive"))
      (node (ref "R19") (pin "2") (pinfunction "2_2") (pintype "passive"))
    )
    (net (code "101") (name "Net-(JP3-Pad1)") (class "Default")
      (node (ref "JP3") (pin "1") (pinfunction "1_1") (pintype "passive"))
      (node (ref "R20") (pin "2") (pinfunction "2_2") (pintype "passive"))
    )
    (net (code "102") (name "Net-(JP3-Pad2)") (class "Default")
      (node (ref "JP3") (pin "2") (pinfunction "2_2") (pintype "passive"))
      (node (ref "R21") (pin "2") (pinfunction "2_2") (pintype "passive"))
    )
    (net (code "103") (name "Net-(JP3-Pad3)") (class "Default")
      (node (ref "JP3") (pin "3") (pinfunction "3_3") (pintype "passive"))
      (node (ref "R22") (pin "2") (pinfunction "2_2") (pintype "passive"))
    )
    (net (code "104") (name "Net-(JP3-Pad4)") (class "Default")
      (node (ref "JP3") (pin "4") (pinfunction "4_4") (pintype "passive"))
      (node (ref "R23") (pin "2") (pinfunction "2_2") (pintype "passive"))
    )
    (net (code "105") (name "Net-(JP3-Pad5)") (class "Default")
      (node (ref "JP3") (pin "5") (pinfunction "5_5") (pintype "passive"))
      (node (ref "R24") (pin "2") (pinfunction "2_2") (pintype "passive"))
    )
    (net (code "106") (name "Net-(JP3-Pad6)") (class "Default")
      (node (ref "JP3") (pin "6") (pinfunction "6_6") (pintype "passive"))
      (node (ref "R25") (pin "2") (pinfunction "2_2") (pintype "passive"))
    )
    (net (code "107") (name "Net-(JP3-Pad7)") (class "Default")
      (node (ref "JP3") (pin "7") (pinfunction "7_7") (pintype "passive"))
      (node (ref "R26") (pin "2") (pinfunction "2_2") (pintype "passive"))
    )
    (net (code "108") (name "Net-(JP3-Pad8)") (class "Default")
      (node (ref "JP3") (pin "8") (pinfunction "8_8") (pintype "passive"))
      (node (ref "R27") (pin "2") (pinfunction "2_2") (pintype "passive"))
    )
    (net (code "109") (name "Net-(JP4-Pad1)") (class "Default")
      (node (ref "JP4") (pin "1") (pinfunction "1_1") (pintype "passive"))
      (node (ref "R28") (pin "2") (pinfunction "2_2") (pintype "passive"))
    )
    (net (code "110") (name "Net-(JP4-Pad2)") (class "Default")
      (node (ref "JP4") (pin "2") (pinfunction "2_2") (pintype "passive"))
      (node (ref "R29") (pin "2") (pinfunction "2_2") (pintype "passive"))
    )
    (net (code "111") (name "Net-(JP4-Pad3)") (class "Default")
      (node (ref "JP4") (pin "3") (pinfunction "3_3") (pintype "passive"))
      (node (ref "R30") (pin "2") (pinfunction "2_2") (pintype "passive"))
    )
    (net (code "112") (name "Net-(JP4-Pad4)") (class "Default")
      (node (ref "JP4") (pin "4") (pinfunction "4_4") (pintype "passive"))
      (node (ref "R31") (pin "2") (pinfunction "2_2") (pintype "passive"))
    )
    (net (code "113") (name "Net-(JP4-Pad5)") (class "Default")
      (node (ref "JP4") (pin "5") (pinfunction "5_5") (pintype "passive"))
      (node (ref "R32") (pin "2") (pinfunction "2_2") (pintype "passive"))
    )
    (net (code "114") (name "Net-(JP4-Pad6)") (class "Default")
      (node (ref "JP4") (pin "6") (pinfunction "6_6") (pintype "passive"))
      (node (ref "R33") (pin "2") (pinfunction "2_2") (pintype "passive"))
    )
    (net (code "115") (name "Net-(JP4-Pad7)") (class "Default")
      (node (ref "JP4") (pin "7") (pinfunction "7_7") (pintype "passive"))
      (node (ref "R34") (pin "2") (pinfunction "2_2") (pintype "passive"))
    )
    (net (code "116") (name "Net-(JP4-Pad8)") (class "Default")
      (node (ref "JP4") (pin "8") (pinfunction "8_8") (pintype "passive"))
      (node (ref "R35") (pin "2") (pinfunction "2_2") (pintype "passive"))
    )
    (net (code "117") (name "Net-(JP5-Pad1)") (class "Default")
      (node (ref "JP5") (pin "1") (pinfunction "1_1") (pintype "passive"))
      (node (ref "R36") (pin "2") (pinfunction "2_2") (pintype "passive"))
    )
    (net (code "118") (name "Net-(JP5-Pad2)") (class "Default")
      (node (ref "JP5") (pin "2") (pinfunction "2_2") (pintype "passive"))
      (node (ref "R37") (pin "2") (pinfunction "2_2") (pintype "passive"))
    )
    (net (code "119") (name "Net-(JP5-Pad3)") (class "Default")
      (node (ref "JP5") (pin "3") (pinfunction "3_3") (pintype "passive"))
      (node (ref "R38") (pin "2") (pinfunction "2_2") (pintype "passive"))
    )
    (net (code "120") (name "Net-(JP5-Pad4)") (class "Default")
      (node (ref "JP5") (pin "4") (pinfunction "4_4") (pintype "passive"))
      (node (ref "R39") (pin "2") (pinfunction "2_2") (pintype "passive"))
    )
    (net (code "121") (name "Net-(JP5-Pad5)") (class "Default")
      (node (ref "JP5") (pin "5") (pinfunction "5_5") (pintype "passive"))
      (node (ref "R40") (pin "2") (pinfunction "2_2") (pintype "passive"))
    )
    (net (code "122") (name "Net-(JP5-Pad6)") (class "Default")
      (node (ref "JP5") (pin "6") (pinfunction "6_6") (pintype "passive"))
      (node (ref "R41") (pin "2") (pinfunction "2_2") (pintype "passive"))
    )
    (net (code "123") (name "Net-(JP5-Pad7)") (class "Default")
      (node (ref "JP5") (pin "7") (pinfunction "7_7") (pintype "passive"))
      (node (ref "R42") (pin "2") (pinfunction "2_2") (pintype "passive"))
    )
    (net (code "124") (name "Net-(JP5-Pad8)") (class "Default")
      (node (ref "JP5") (pin "8") (pinfunction "8_8") (pintype "passive"))
      (node (ref "R43") (pin "2") (pinfunction "2_2") (pintype "passive"))
    )
    (net (code "125") (name "Net-(JP6-Pad1)") (class "Default")
      (node (ref "JP6") (pin "1") (pinfunction "1_1") (pintype "passive"))
      (node (ref "R44") (pin "2") (pinfunction "2_2") (pintype "passive"))
    )
    (net (code "126") (name "Net-(JP6-Pad2)") (class "Default")
      (node (ref "JP6") (pin "2") (pinfunction "2_2") (pintype "passive"))
      (node (ref "R45") (pin "2") (pinfunction "2_2") (pintype "passive"))
    )
    (net (code "127") (name "Net-(JP6-Pad3)") (class "Default")
      (node (ref "JP6") (pin "3") (pinfunction "3_3") (pintype "passive"))
      (node (ref "R46") (pin "2") (pinfunction "2_2") (pintype "passive"))
    )
    (net (code "128") (name "Net-(JP6-Pad4)") (class "Default")
      (node (ref "JP6") (pin "4") (pinfunction "4_4") (pintype "passive"))
      (node (ref "R47") (pin "2") (pinfunction "2_2") (pintype "passive"))
    )
    (net (code "129") (name "Net-(JP6-Pad5)") (class "Default")
      (node (ref "JP6") (pin "5") (pinfunction "5_5") (pintype "passive"))
      (node (ref "R48") (pin "2") (pinfunction "2_2") (pintype "passive"))
    )
    (net (code "130") (name "Net-(JP6-Pad6)") (class "Default")
      (node (ref "JP6") (pin "6") (pinfunction "6_6") (pintype "passive"))
      (node (ref "R49") (pin "2") (pinfunction "2_2") (pintype "passive"))
    )
    (net (code "131") (name "Net-(JP6-Pad7)") (class "Default")
      (node (ref "JP6") (pin "7") (pinfunction "7_7") (pintype "passive"))
      (node (ref "R50") (pin "2") (pinfunction "2_2") (pintype "passive"))
    )
    (net (code "132") (name "Net-(JP6-Pad8)") (class "Default")
      (node (ref "JP6") (pin "8") (pinfunction "8_8") (pintype "passive"))
      (node (ref "R51") (pin "2") (pinfunction "2_2") (pintype "passive"))
    )
    (net (code "133") (name "Net-(JP8-Pad1)") (class "Default")
      (node (ref "JP8") (pin "1") (pinfunction "1_1") (pintype "passive"))
      (node (ref "R60") (pin "2") (pinfunction "2_2") (pintype "passive"))
    )
    (net (code "134") (name "Net-(JP8-Pad2)") (class "Default")
      (node (ref "JP8") (pin "2") (pinfunction "2_2") (pintype "passive"))
      (node (ref "R61") (pin "2") (pinfunction "2_2") (pintype "passive"))
    )
    (net (code "135") (name "Net-(JP8-Pad3)") (class "Default")
      (node (ref "JP8") (pin "3") (pinfunction "3_3") (pintype "passive"))
      (node (ref "R62") (pin "2") (pinfunction "2_2") (pintype "passive"))
    )
    (net (code "136") (name "Net-(JP8-Pad4)") (class "Default")
      (node (ref "JP8") (pin "4") (pinfunction "4_4") (pintype "passive"))
      (node (ref "R63") (pin "2") (pinfunction "2_2") (pintype "passive"))
    )
    (net (code "137") (name "Net-(JP8-Pad5)") (class "Default")
      (node (ref "JP8") (pin "5") (pinfunction "5_5") (pintype "passive"))
      (node (ref "R64") (pin "2") (pinfunction "2_2") (pintype "passive"))
    )
    (net (code "138") (name "Net-(JP8-Pad6)") (class "Default")
      (node (ref "JP8") (pin "6") (pinfunction "6_6") (pintype "passive"))
      (node (ref "R65") (pin "2") (pinfunction "2_2") (pintype "passive"))
    )
    (net (code "139") (name "Net-(JP8-Pad7)") (class "Default")
      (node (ref "JP8") (pin "7") (pinfunction "7_7") (pintype "passive"))
      (node (ref "R66") (pin "2") (pinfunction "2_2") (pintype "passive"))
    )
    (net (code "140") (name "Net-(JP8-Pad8)") (class "Default")
      (node (ref "JP8") (pin "8") (pinfunction "8_8") (pintype "passive"))
      (node (ref "R67") (pin "2") (pinfunction "2_2") (pintype "passive"))
    )
    (net (code "141") (name "Net-(JP9-Pad1)") (class "Default")
      (node (ref "JP9") (pin "1") (pinfunction "1_1") (pintype "passive"))
      (node (ref "R68") (pin "2") (pinfunction "2_2") (pintype "passive"))
    )
    (net (code "142") (name "Net-(JP9-Pad2)") (class "Default")
      (node (ref "JP9") (pin "2") (pinfunction "2_2") (pintype "passive"))
      (node (ref "R69") (pin "2") (pinfunction "2_2") (pintype "passive"))
    )
    (net (code "143") (name "Net-(JP9-Pad3)") (class "Default")
      (node (ref "JP9") (pin "3") (pinfunction "3_3") (pintype "passive"))
      (node (ref "R70") (pin "2") (pinfunction "2_2") (pintype "passive"))
    )
    (net (code "144") (name "Net-(JP9-Pad4)") (class "Default")
      (node (ref "JP9") (pin "4") (pinfunction "4_4") (pintype "passive"))
      (node (ref "R71") (pin "2") (pinfunction "2_2") (pintype "passive"))
    )
    (net (code "145") (name "Net-(JP9-Pad5)") (class "Default")
      (node (ref "JP9") (pin "5") (pinfunction "5_5") (pintype "passive"))
      (node (ref "R72") (pin "2") (pinfunction "2_2") (pintype "passive"))
    )
    (net (code "146") (name "Net-(JP9-Pad6)") (class "Default")
      (node (ref "JP9") (pin "6") (pinfunction "6_6") (pintype "passive"))
      (node (ref "R73") (pin "2") (pinfunction "2_2") (pintype "passive"))
    )
    (net (code "147") (name "Net-(JP9-Pad7)") (class "Default")
      (node (ref "JP9") (pin "7") (pinfunction "7_7") (pintype "passive"))
      (node (ref "R74") (pin "2") (pinfunction "2_2") (pintype "passive"))
    )
    (net (code "148") (name "Net-(JP9-Pad8)") (class "Default")
      (node (ref "JP9") (pin "8") (pinfunction "8_8") (pintype "passive"))
      (node (ref "R75") (pin "2") (pinfunction "2_2") (pintype "passive"))
    )
    (net (code "149") (name "Net-(Q1-PadB)") (class "Default")
      (node (ref "Q1") (pin "B") (pinfunction "B_B") (pintype "passive"))
      (node (ref "R3") (pin "2") (pinfunction "2_2") (pintype "passive"))
    )
    (net (code "150") (name "Net-(Q2-PadB)") (class "Default")
      (node (ref "Q2") (pin "B") (pinfunction "B_B") (pintype "passive"))
      (node (ref "R2") (pin "2") (pinfunction "2_2") (pintype "passive"))
    )
    (net (code "151") (name "Net-(Q3-PadB)") (class "Default")
      (node (ref "Q3") (pin "B") (pinfunction "B_B") (pintype "passive"))
      (node (ref "R1") (pin "2") (pinfunction "2_2") (pintype "passive"))
    )
    (net (code "152") (name "Net-(R1-Pad1)") (class "Default")
      (node (ref "R1") (pin "1") (pinfunction "1_1") (pintype "passive"))
      (node (ref "U$2") (pin "GP17") (pinfunction "GP17_GP17") (pintype "bidirectional"))
    )
    (net (code "153") (name "Net-(R2-Pad1)") (class "Default")
      (node (ref "R2") (pin "1") (pinfunction "1_1") (pintype "passive"))
      (node (ref "U$2") (pin "GP16") (pinfunction "GP16_GP16") (pintype "bidirectional"))
    )
    (net (code "154") (name "Net-(R3-Pad1)") (class "Default")
      (node (ref "R3") (pin "1") (pinfunction "1_1") (pintype "passive"))
      (node (ref "U$2") (pin "GP18") (pinfunction "GP18_GP18") (pintype "bidirectional"))
    )
    (net (code "155") (name "Net-(R79-Pad2)") (class "Default")
      (node (ref "R79") (pin "2") (pinfunction "2_2") (pintype "passive"))
      (node (ref "SV1") (pin "1") (pinfunction "1_1") (pintype "passive"))
      (node (ref "U$2") (pin "GP1") (pinfunction "GP1_GP1") (pintype "bidirectional"))
    )
    (net (code "156") (name "Net-(R80-Pad2)") (class "Default")
      (node (ref "R80") (pin "2") (pinfunction "2_2") (pintype "passive"))
      (node (ref "SV1") (pin "2") (pinfunction "2_2") (pintype "passive"))
      (node (ref "U$2") (pin "GP0") (pinfunction "GP0_GP0") (pintype "bidirectional"))
    )
    (net (code "157") (name "Net-(SV2-Pad2)") (class "Default")
      (node (ref "SV2") (pin "2") (pinfunction "2_2") (pintype "passive"))
      (node (ref "U$2") (pin "GP28") (pinfunction "GP28_GP28") (pintype "bidirectional"))
    )
    (net (code "158") (name "Net-(SV2-Pad3)") (class "Default")
      (node (ref "SV2") (pin "3") (pinfunction "3_3") (pintype "passive"))
      (node (ref "U$2") (pin "GP27") (pinfunction "GP27_GP27") (pintype "bidirectional"))
    )
    (net (code "159") (name "Net-(SV2-Pad4)") (class "Default")
      (node (ref "SV2") (pin "4") (pinfunction "4_4") (pintype "passive"))
      (node (ref "U$2") (pin "GP26") (pinfunction "GP26_GP26") (pintype "bidirectional"))
    )
    (net (code "160") (name "Net-(T1-B)") (class "Default")
      (node (ref "R53") (pin "2") (pinfunction "2_2") (pintype "passive"))
      (node (ref "T1") (pin "1") (pinfunction "B_1") (pintype "passive"))
    )
    (net (code "161") (name "Net-(T1-C)") (class "Default")
      (node (ref "JP7") (pin "2") (pinfunction "2_2") (pintype "passive"))
      (node (ref "T1") (pin "2") (pinfunction "C_2") (pintype "passive"))
    )
    (net (code "162") (name "Net-(T2-B)") (class "Default")
      (node (ref "R54") (pin "2") (pinfunction "2_2") (pintype "passive"))
      (node (ref "T2") (pin "1") (pinfunction "B_1") (pintype "passive"))
    )
    (net (code "163") (name "Net-(T2-C)") (class "Default")
      (node (ref "JP7") (pin "3") (pinfunction "3_3") (pintype "passive"))
      (node (ref "T2") (pin "2") (pinfunction "C_2") (pintype "passive"))
    )
    (net (code "164") (name "Net-(T3-B)") (class "Default")
      (node (ref "R55") (pin "2") (pinfunction "2_2") (pintype "passive"))
      (node (ref "T3") (pin "1") (pinfunction "B_1") (pintype "passive"))
    )
    (net (code "165") (name "Net-(T3-C)") (class "Default")
      (node (ref "JP7") (pin "4") (pinfunction "4_4") (pintype "passive"))
      (node (ref "T3") (pin "2") (pinfunction "C_2") (pintype "passive"))
    )
    (net (code "166") (name "Net-(T4-B)") (class "Default")
      (node (ref "R56") (pin "2") (pinfunction "2_2") (pintype "passive"))
      (node (ref "T4") (pin "1") (pinfunction "B_1") (pintype "passive"))
    )
    (net (code "167") (name "Net-(T4-C)") (class "Default")
      (node (ref "JP7") (pin "5") (pinfunction "5_5") (pintype "passive"))
      (node (ref "T4") (pin "2") (pinfunction "C_2") (pintype "passive"))
    )
    (net (code "168") (name "Net-(T5-B)") (class "Default")
      (node (ref "R57") (pin "2") (pinfunction "2_2") (pintype "passive"))
      (node (ref "T5") (pin "1") (pinfunction "B_1") (pintype "passive"))
    )
    (net (code "169") (name "Net-(T5-C)") (class "Default")
      (node (ref "JP7") (pin "6") (pinfunction "6_6") (pintype "passive"))
      (node (ref "T5") (pin "2") (pinfunction "C_2") (pintype "passive"))
    )
    (net (code "170") (name "Net-(T6-B)") (class "Default")
      (node (ref "R58") (pin "2") (pinfunction "2_2") (pintype "passive"))
      (node (ref "T6") (pin "1") (pinfunction "B_1") (pintype "passive"))
    )
    (net (code "171") (name "Net-(T6-C)") (class "Default")
      (node (ref "JP7") (pin "7") (pinfunction "7_7") (pintype "passive"))
      (node (ref "T6") (pin "2") (pinfunction "C_2") (pintype "passive"))
    )
    (net (code "172") (name "Net-(T7-B)") (class "Default")
      (node (ref "R52") (pin "2") (pinfunction "2_2") (pintype "passive"))
      (node (ref "T7") (pin "1") (pinfunction "B_1") (pintype "passive"))
    )
    (net (code "173") (name "Net-(T7-C)") (class "Default")
      (node (ref "JP7") (pin "1") (pinfunction "1_1") (pintype "passive"))
      (node (ref "T7") (pin "2") (pinfunction "C_2") (pintype "passive"))
    )
    (net (code "174") (name "Net-(T8-B)") (class "Default")
      (node (ref "R59") (pin "2") (pinfunction "2_2") (pintype "passive"))
      (node (ref "T8") (pin "1") (pinfunction "B_1") (pintype "passive"))
    )
    (net (code "175") (name "Net-(T8-C)") (class "Default")
      (node (ref "JP7") (pin "8") (pinfunction "8_8") (pintype "passive"))
      (node (ref "T8") (pin "2") (pinfunction "C_2") (pintype "passive"))
    )
    (net (code "176") (name "VCC") (class "Default")
      (node (ref "IC1") (pin "10") (pinfunction "SCL_10") (pintype "input"))
      (node (ref "IC2") (pin "10") (pinfunction "SCL_10") (pintype "input"))
      (node (ref "IC3") (pin "10") (pinfunction "SCL_10") (pintype "input"))
      (node (ref "IC4") (pin "10") (pinfunction "SCL_10") (pintype "input"))
      (node (ref "IC5") (pin "10") (pinfunction "SCL_10") (pintype "input"))
      (node (ref "IC6") (pin "10") (pinfunction "SCL_10") (pintype "input"))
      (node (ref "IC7") (pin "10") (pinfunction "SCL_10") (pintype "input"))
      (node (ref "IC8") (pin "10") (pinfunction "SCL_10") (pintype "input"))
      (node (ref "IC9") (pin "10") (pinfunction "SCL_10") (pintype "input"))
      (node (ref "J2") (pin "1") (pinfunction "1_1") (pintype "passive"))
      (node (ref "R76") (pin "2") (pinfunction "2_2") (pintype "passive"))
      (node (ref "R77") (pin "2") (pinfunction "2_2") (pintype "passive"))
      (node (ref "R78") (pin "2") (pinfunction "2_2") (pintype "passive"))
      (node (ref "SV1") (pin "3") (pinfunction "3_3") (pintype "passive"))
      (node (ref "SV2") (pin "5") (pinfunction "5_5") (pintype "passive"))
      (node (ref "U$2") (pin "VSYS") (pinfunction "VSYS_VSYS") (pintype "bidirectional"))
    )
    (net (code "177") (name "unconnected-(IC7A-QH*-Pad9)") (class "Default")
      (node (ref "IC7") (pin "9") (pinfunction "QH*_9") (pintype "tri_state"))
    )
    (net (code "178") (name "unconnected-(J2-Pad2)") (class "Default")
      (node (ref "J2") (pin "2") (pinfunction "2_2") (pintype "passive"))
    )
    (net (code "179") (name "unconnected-(PAD1-P-Pad1)") (class "Default")
      (node (ref "PAD1") (pin "1") (pinfunction "P_1") (pintype "passive"))
    )
    (net (code "180") (name "unconnected-(PAD2-P-Pad1)") (class "Default")
      (node (ref "PAD2") (pin "1") (pinfunction "P_1") (pintype "passive"))
    )
    (net (code "181") (name "unconnected-(PAD3-P-Pad1)") (class "Default")
      (node (ref "PAD3") (pin "1") (pinfunction "P_1") (pintype "passive"))
    )
    (net (code "182") (name "unconnected-(PAD4-P-Pad1)") (class "Default")
      (node (ref "PAD4") (pin "1") (pinfunction "P_1") (pintype "passive"))
    )
    (net (code "183") (name "unconnected-(U$2-ADC_VREF-PadADC)") (class "Default")
      (node (ref "U$2") (pin "ADC") (pinfunction "ADC_VREF_ADC") (pintype "bidirectional"))
    )
    (net (code "184") (name "unconnected-(U$2-Pad3V3(OUT))") (class "Default")
      (node (ref "U$2") (pin "3V3(OUT)") (pinfunction "3V3(OUT)_3V3(OUT)") (pintype "bidirectional"))
    )
    (net (code "185") (name "unconnected-(U$2-Pad3V3_EN)") (class "Default")
      (node (ref "U$2") (pin "3V3_EN") (pinfunction "3V3_EN_3V3_EN") (pintype "bidirectional"))
    )
    (net (code "186") (name "unconnected-(U$2-PadGND1)") (class "Default")
      (node (ref "U$2") (pin "GND1") (pinfunction "GND1_GND1") (pintype "bidirectional"))
    )
    (net (code "187") (name "unconnected-(U$2-PadGND2)") (class "Default")
      (node (ref "U$2") (pin "GND2") (pinfunction "GND2_GND2") (pintype "bidirectional"))
    )
    (net (code "188") (name "unconnected-(U$2-PadGND3)") (class "Default")
      (node (ref "U$2") (pin "GND3") (pinfunction "GND3_GND3") (pintype "bidirectional"))
    )
    (net (code "189") (name "unconnected-(U$2-PadGND4)") (class "Default")
      (node (ref "U$2") (pin "GND4") (pinfunction "GND4_GND4") (pintype "bidirectional"))
    )
    (net (code "190") (name "unconnected-(U$2-PadGND5)") (class "Default")
      (node (ref "U$2") (pin "GND5") (pinfunction "GND5_GND5") (pintype "bidirectional"))
    )
    (net (code "191") (name "unconnected-(U$2-PadGND6)") (class "Default")
      (node (ref "U$2") (pin "GND6") (pinfunction "GND6_GND6") (pintype "bidirectional"))
    )
    (net (code "192") (name "unconnected-(U$2-PadGND7)") (class "Default")
      (node (ref "U$2") (pin "GND7") (pinfunction "GND7_GND7") (pintype "bidirectional"))
    )
    (net (code "193") (name "unconnected-(U$2-PadGP2)") (class "Default")
      (node (ref "U$2") (pin "GP2") (pinfunction "GP2_GP2") (pintype "bidirectional"))
    )
    (net (code "194") (name "unconnected-(U$2-PadGP3)") (class "Default")
      (node (ref "U$2") (pin "GP3") (pinfunction "GP3_GP3") (pintype "bidirectional"))
    )
    (net (code "195") (name "unconnected-(U$2-PadGP4)") (class "Default")
      (node (ref "U$2") (pin "GP4") (pinfunction "GP4_GP4") (pintype "bidirectional"))
    )
    (net (code "196") (name "unconnected-(U$2-PadGP5)") (class "Default")
      (node (ref "U$2") (pin "GP5") (pinfunction "GP5_GP5") (pintype "bidirectional"))
    )
    (net (code "197") (name "unconnected-(U$2-PadGP6)") (class "Default")
      (node (ref "U$2") (pin "GP6") (pinfunction "GP6_GP6") (pintype "bidirectional"))
    )
    (net (code "198") (name "unconnected-(U$2-PadGP7)") (class "Default")
      (node (ref "U$2") (pin "GP7") (pinfunction "GP7_GP7") (pintype "bidirectional"))
    )
    (net (code "199") (name "unconnected-(U$2-PadGP8)") (class "Default")
      (node (ref "U$2") (pin "GP8") (pinfunction "GP8_GP8") (pintype "bidirectional"))
    )
    (net (code "200") (name "unconnected-(U$2-PadGP9)") (class "Default")
      (node (ref "U$2") (pin "GP9") (pinfunction "GP9_GP9") (pintype "bidirectional"))
    )
    (net (code "201") (name "unconnected-(U$2-PadGP10)") (class "Default")
      (node (ref "U$2") (pin "GP10") (pinfunction "GP10_GP10") (pintype "bidirectional"))
    )
    (net (code "202") (name "unconnected-(U$2-PadGP11)") (class "Default")
      (node (ref "U$2") (pin "GP11") (pinfunction "GP11_GP11") (pintype "bidirectional"))
    )
    (net (code "203") (name "unconnected-(U$2-PadGP12)") (class "Default")
      (node (ref "U$2") (pin "GP12") (pinfunction "GP12_GP12") (pintype "bidirectional"))
    )
    (net (code "204") (name "unconnected-(U$2-PadGP13)") (class "Default")
      (node (ref "U$2") (pin "GP13") (pinfunction "GP13_GP13") (pintype "bidirectional"))
    )
    (net (code "205") (name "unconnected-(U$2-PadGP14)") (class "Default")
      (node (ref "U$2") (pin "GP14") (pinfunction "GP14_GP14") (pintype "bidirectional"))
    )
    (net (code "206") (name "unconnected-(U$2-PadGP15)") (class "Default")
      (node (ref "U$2") (pin "GP15") (pinfunction "GP15_GP15") (pintype "bidirectional"))
    )
    (net (code "207") (name "unconnected-(U$2-PadGP19)") (class "Default")
      (node (ref "U$2") (pin "GP19") (pinfunction "GP19_GP19") (pintype "bidirectional"))
    )
    (net (code "208") (name "unconnected-(U$2-PadGP20)") (class "Default")
      (node (ref "U$2") (pin "GP20") (pinfunction "GP20_GP20") (pintype "bidirectional"))
    )
    (net (code "209") (name "unconnected-(U$2-PadGP21)") (class "Default")
      (node (ref "U$2") (pin "GP21") (pinfunction "GP21_GP21") (pintype "bidirectional"))
    )
    (net (code "210") (name "unconnected-(U$2-PadGP22)") (class "Default")
      (node (ref "U$2") (pin "GP22") (pinfunction "GP22_GP22") (pintype "bidirectional"))
    )
    (net (code "211") (name "unconnected-(U$2-PadRUN)") (class "Default")
      (node (ref "U$2") (pin "RUN") (pinfunction "RUN_RUN") (pintype "bidirectional"))
    )
    (net (code "212") (name "unconnected-(U$2-PadVBUS)") (class "Default")
      (node (ref "U$2") (pin "VBUS") (pinfunction "VBUS_VBUS") (pintype "bidirectional"))
    )
  )
)
